# non_inverting_amplifier.net
KiCad netlist of a schematic drawn in EAGLE
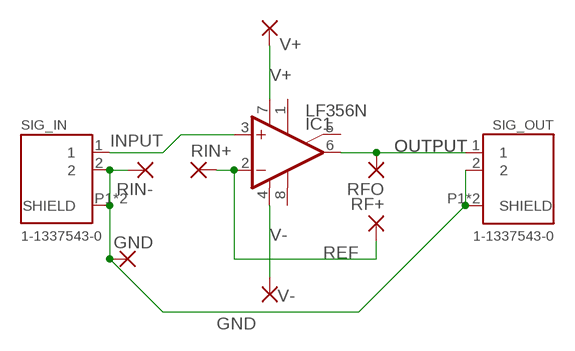
[diagram p0: schematic, sheet 1]

(export (version "E")
  (design (tool "Eeschema 10.0.6"))
  (components
    (comp (ref "GND")
      (value "2,54/1,1")
      (footprint "eagle-import:2,54_1,1")
      (libsource (lib "eagle-import") (part "2,54/1,1"))
    )
    (comp (ref "IC1")
      (value "LF356N")
      (footprint "eagle-import:DIL08")
      (libsource (lib "eagle-import") (part "LF356N"))
    )
    (comp (ref "RF+")
      (value "2,54/1,1")
      (footprint "eagle-import:2,54_1,1")
      (libsource (lib "eagle-import") (part "2,54/1,1"))
    )
    (comp (ref "RFO")
      (value "2,54/1,1")
      (footprint "eagle-import:2,54_1,1")
      (libsource (lib "eagle-import") (part "2,54/1,1"))
    )
    (comp (ref "RIN+")
      (value "2,54/1,1")
      (footprint "eagle-import:2,54_1,1")
      (libsource (lib "eagle-import") (part "2,54/1,1"))
    )
    (comp (ref "RIN-")
      (value "2,54/1,1")
      (footprint "eagle-import:2,54_1,1")
      (libsource (lib "eagle-import") (part "2,54/1,1"))
    )
    (comp (ref "SIG_IN")
      (value "1-1337543-0")
      (footprint "eagle-import:CONN_1-1337543-0")
      (fields (field (name "DIGI-KEY_PART_NUMBER") "A97553-ND") (field (name "MF") "TE Connectivity"))
      (libsource (lib "eagle-import") (part "1-1337543-0"))
    )
    (comp (ref "SIG_OUT")
      (value "1-1337543-0")
      (footprint "eagle-import:CONN_1-1337543-0")
      (fields (field (name "DIGI-KEY_PART_NUMBER") "A97553-ND") (field (name "MF") "TE Connectivity"))
      (libsource (lib "eagle-import") (part "1-1337543-0"))
    )
    (comp (ref "V+")
      (value "2,54/1,1")
      (footprint "eagle-import:2,54_1,1")
      (libsource (lib "eagle-import") (part "2,54/1,1"))
    )
    (comp (ref "V-")
      (value "2,54/1,1")
      (footprint "eagle-import:2,54_1,1")
      (libsource (lib "eagle-import") (part "2,54/1,1"))
    )
  )
  (nets
    (net (code "1") (name "/GND") (class "Default")
      (node (ref "GND") (pin "1") (pinfunction "P_1") (pintype "passive"))
      (node (ref "RIN-") (pin "1") (pinfunction "P_1") (pintype "passive"))
      (node (ref "SIG_IN") (pin "2") (pinfunction "2_2") (pintype "passive"))
      (node (ref "SIG_IN") (pin "P1") (pinfunction "SHIELD_P1") (pintype "passive"))
      (node (ref "SIG_IN") (pin "P2") (pinfunction "SHIELD_P2") (pintype "passive"))
      (node (ref "SIG_OUT") (pin "2") (pinfunction "2_2") (pintype "passive"))
      (node (ref "SIG_OUT") (pin "P1") (pinfunction "SHIELD_P1") (pintype "passive"))
      (node (ref "SIG_OUT") (pin "P2") (pinfunction "SHIELD_P2") (pintype "passive"))
    )
    (net (code "2") (name "/INPUT") (class "Default")
      (node (ref "IC1") (pin "3") (pinfunction "+IN_3") (pintype "input"))
      (node (ref "SIG_IN") (pin "1") (pinfunction "1_1") (pintype "passive"))
    )
    (net (code "3") (name "/OUTPUT") (class "Default")
      (node (ref "IC1") (pin "6") (pinfunction "OUT_6") (pintype "output"))
      (node (ref "RFO") (pin "1") (pinfunction "P_1") (pintype "passive"))
      (node (ref "SIG_OUT") (pin "1") (pinfunction "1_1") (pintype "passive"))
    )
    (net (code "4") (name "/REF") (class "Default")
      (node (ref "IC1") (pin "2") (pinfunction "-IN_2") (pintype "input"))
      (node (ref "RF+") (pin "1") (pinfunction "P_1") (pintype "passive"))
      (node (ref "RIN+") (pin "1") (pinfunction "P_1") (pintype "passive"))
    )
    (net (code "5") (name "/V+") (class "Default")
      (node (ref "IC1") (pin "7") (pinfunction "V+_7") (pintype "power_in"))
      (node (ref "V+") (pin "1") (pinfunction "P_1") (pintype "passive"))
    )
    (net (code "6") (name "/V-") (class "Default")
      (node (ref "IC1") (pin "4") (pinfunction "V-_4") (pintype "power_in"))
      (node (ref "V-") (pin "1") (pinfunction "P_1") (pintype "passive"))
    )
    (net (code "7") (name "unconnected-(IC1-ON1-Pad1)") (class "Default")
      (node (ref "IC1") (pin "1") (pinfunction "ON1_1") (pintype "passive"))
    )
    (net (code "8") (name "unconnected-(IC1-ON2-Pad5)") (class "Default")
      (node (ref "IC1") (pin "5") (pinfunction "ON2_5") (pintype "passive"))
    )
    (net (code "9") (name "unconnected-(IC1-OPT-Pad8)") (class "Default")
      (node (ref "IC1") (pin "8") (pinfunction "OPT_8") (pintype "passive"))
    )
  )
)
